# mainboard.net
KiCad netlist of a schematic drawn in EAGLE
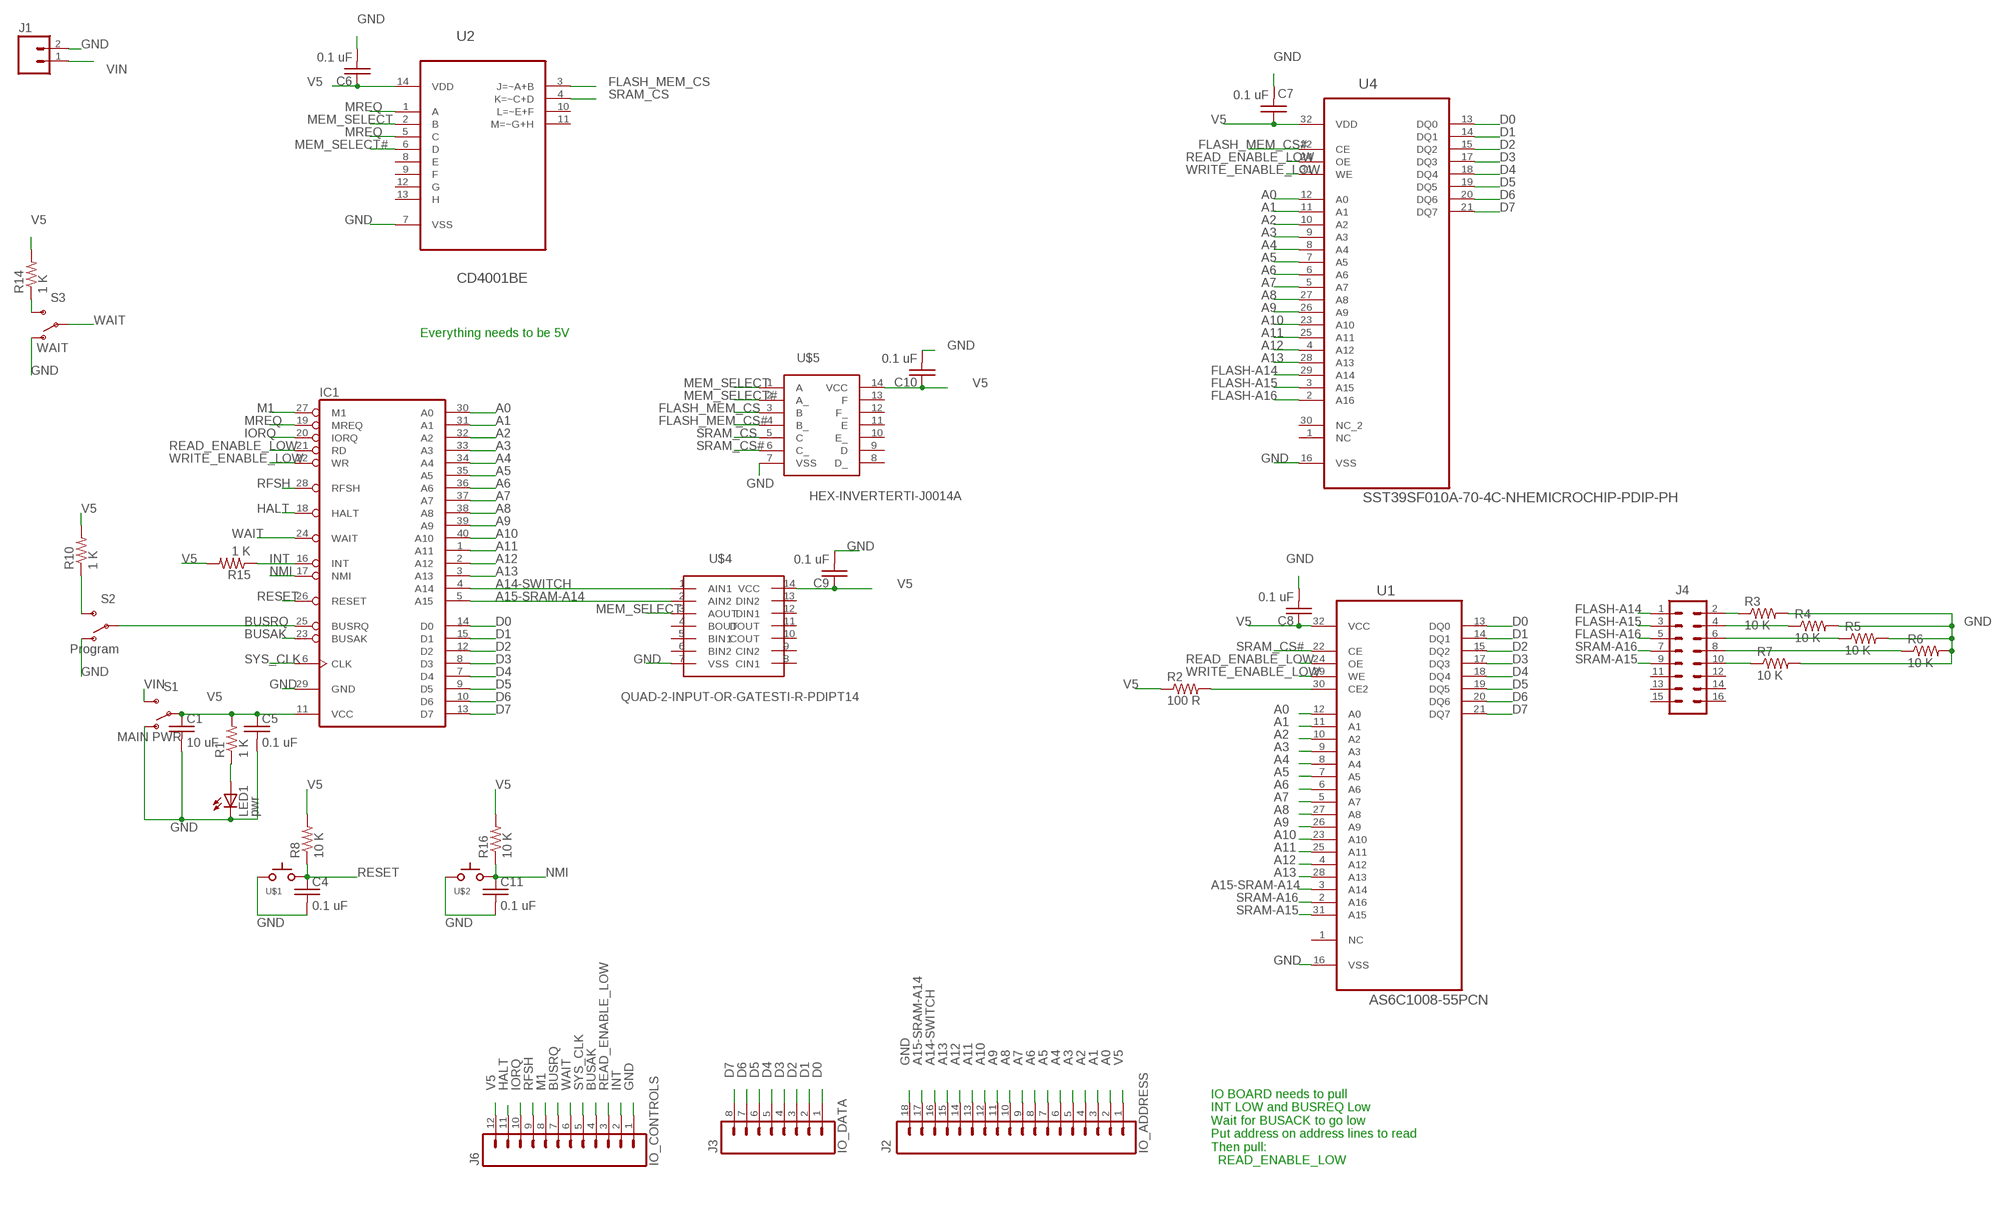
[diagram p0: schematic, sheet 1]
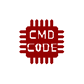
[diagram p1: schematic, sheet 2]

(export (version "E")
  (design (tool "Eeschema 10.0.6"))
  (components
    (comp (ref "C1")
      (value "10 uF")
      (footprint "eagle-import:C0805K")
      (libsource (lib "eagle-import") (part "C-USC0805K"))
    )
    (comp (ref "C4")
      (value "0.1 uF")
      (footprint "eagle-import:C0805K")
      (libsource (lib "eagle-import") (part "C-USC0805K"))
    )
    (comp (ref "C5")
      (value "0.1 uF")
      (footprint "eagle-import:C0805K")
      (libsource (lib "eagle-import") (part "C-USC0805K"))
    )
    (comp (ref "C6")
      (value "0.1 uF")
      (footprint "eagle-import:C0805K")
      (libsource (lib "eagle-import") (part "C-USC0805K"))
    )
    (comp (ref "C7")
      (value "0.1 uF")
      (footprint "eagle-import:C0805K")
      (libsource (lib "eagle-import") (part "C-USC0805K"))
    )
    (comp (ref "C8")
      (value "0.1 uF")
      (footprint "eagle-import:C0805K")
      (libsource (lib "eagle-import") (part "C-USC0805K"))
    )
    (comp (ref "C9")
      (value "0.1 uF")
      (footprint "eagle-import:C0805K")
      (libsource (lib "eagle-import") (part "C-USC0805K"))
    )
    (comp (ref "C10")
      (value "0.1 uF")
      (footprint "eagle-import:C0805K")
      (libsource (lib "eagle-import") (part "C-USC0805K"))
    )
    (comp (ref "C11")
      (value "0.1 uF")
      (footprint "eagle-import:C0805K")
      (libsource (lib "eagle-import") (part "C-USC0805K"))
    )
    (comp (ref "IC1")
      (value "Z80CPU")
      (footprint "eagle-import:DIL40")
      (libsource (lib "eagle-import") (part "Z80CPU"))
    )
    (comp (ref "J1")
      (value "M02PTH")
      (footprint "eagle-import:1X02")
      (libsource (lib "eagle-import") (part "M02PTH"))
    )
    (comp (ref "J2")
      (value "IO_ADDRESS")
      (footprint "eagle-import:1X18")
      (libsource (lib "eagle-import") (part "M18_"))
    )
    (comp (ref "J3")
      (value "IO_DATA")
      (footprint "eagle-import:1X08_LOCK_LONGPADS")
      (libsource (lib "eagle-import") (part "M08LOCK_LONGPADS"))
    )
    (comp (ref "J4")
      (value "M08X2")
      (footprint "eagle-import:2X8")
      (libsource (lib "eagle-import") (part "M08X2"))
    )
    (comp (ref "J6")
      (value "IO_CONTROLS")
      (footprint "eagle-import:1X12_LONGPADS")
      (libsource (lib "eagle-import") (part "M12LONGPADS"))
    )
    (comp (ref "LED1")
      (value "pwr")
      (footprint "eagle-import:LED-1206")
      (libsource (lib "eagle-import") (part "LED1206"))
    )
    (comp (ref "R1")
      (value "1 K")
      (footprint "eagle-import:0805")
      (libsource (lib "eagle-import") (part "RESISTOR0805-RES"))
    )
    (comp (ref "R2")
      (value "100 R")
      (footprint "eagle-import:0805")
      (libsource (lib "eagle-import") (part "RESISTOR0805-RES"))
    )
    (comp (ref "R3")
      (value "10 K")
      (footprint "eagle-import:0805")
      (libsource (lib "eagle-import") (part "RESISTOR0805-RES"))
    )
    (comp (ref "R4")
      (value "10 K")
      (footprint "eagle-import:0805")
      (libsource (lib "eagle-import") (part "RESISTOR0805-RES"))
    )
    (comp (ref "R5")
      (value "10 K")
      (footprint "eagle-import:0805")
      (libsource (lib "eagle-import") (part "RESISTOR0805-RES"))
    )
    (comp (ref "R6")
      (value "10 K")
      (footprint "eagle-import:0805")
      (libsource (lib "eagle-import") (part "RESISTOR0805-RES"))
    )
    (comp (ref "R7")
      (value "10 K")
      (footprint "eagle-import:0805")
      (libsource (lib "eagle-import") (part "RESISTOR0805-RES"))
    )
    (comp (ref "R8")
      (value "10 K")
      (footprint "eagle-import:0805")
      (libsource (lib "eagle-import") (part "RESISTOR0805-RES"))
    )
    (comp (ref "R10")
      (value "1 K")
      (footprint "eagle-import:0805")
      (libsource (lib "eagle-import") (part "RESISTOR0805-RES"))
    )
    (comp (ref "R14")
      (value "1 K")
      (footprint "eagle-import:0805")
      (libsource (lib "eagle-import") (part "RESISTOR0805-RES"))
    )
    (comp (ref "R15")
      (value "1 K")
      (footprint "eagle-import:0805")
      (libsource (lib "eagle-import") (part "RESISTOR0805-RES"))
    )
    (comp (ref "R16")
      (value "10 K")
      (footprint "eagle-import:0805")
      (libsource (lib "eagle-import") (part "RESISTOR0805-RES"))
    )
    (comp (ref "S1")
      (value "MAIN PWR")
      (footprint "eagle-import:SWITCH-SPDT_KIT")
      (libsource (lib "eagle-import") (part "SWITCH-SPSTKIT"))
    )
    (comp (ref "S2")
      (value "Program")
      (footprint "eagle-import:SWITCH-SPDT_KIT")
      (libsource (lib "eagle-import") (part "SWITCH-SPSTKIT"))
    )
    (comp (ref "S3")
      (value "WAIT")
      (footprint "eagle-import:SWITCH-SPDT_KIT")
      (libsource (lib "eagle-import") (part "SWITCH-SPSTKIT"))
    )
    (comp (ref "U$1")
      (value "SWITCH_TACTILETACTILE-2PIN-NARROW")
      (footprint "eagle-import:TACTILE-2PIN-NARROW")
      (libsource (lib "eagle-import") (part "SWITCH_TACTILETACTILE-2PIN-NARROW"))
    )
    (comp (ref "U$2")
      (value "SWITCH_TACTILETACTILE-2PIN-NARROW")
      (footprint "eagle-import:TACTILE-2PIN-NARROW")
      (libsource (lib "eagle-import") (part "SWITCH_TACTILETACTILE-2PIN-NARROW"))
    )
    (comp (ref "U$4")
      (value "QUAD-2-INPUT-OR-GATESTI-R-PDIPT14")
      (footprint "eagle-import:DIP762W36P254L1981H508Q14B")
      (libsource (lib "eagle-import") (part "QUAD-2-INPUT-OR-GATESTI-R-PDIPT14"))
    )
    (comp (ref "U$5")
      (value "HEX-INVERTERTI-J0014A")
      (footprint "eagle-import:DIP797W66P254L1954H508Q14B")
      (libsource (lib "eagle-import") (part "HEX-INVERTERTI-J0014A"))
    )
    (comp (ref "U1")
      (value "AS6C1008-55PCN")
      (footprint "eagle-import:DIP254P1524X393-32")
      (fields (field (name "MF") "Alliance Memory,"))
      (libsource (lib "eagle-import") (part "AS6C1008-55PCN"))
    )
    (comp (ref "U2")
      (value "CD4001BE")
      (footprint "eagle-import:DIP254P762X508-14")
      (fields (field (name "MF") "Texas Instruments"))
      (libsource (lib "eagle-import") (part "CD4001BE"))
    )
    (comp (ref "U4")
      (value "SST39SF010A-70-4C-NHEMICROCHIP-PDIP-PH")
      (footprint "eagle-import:DIP1574W53P254L4191H508Q32B")
      (fields (field (name "MP") "SST39SF010A-70-4C-NHE"))
      (libsource (lib "eagle-import") (part "SST39SF010A-70-4C-NHEMICROCHIP-PDIP-PH"))
    )
    (comp (ref "U$3")
      (value "CMD_C0DE_LOGOCMD_CODE_LOGO_SILK")
      (footprint "eagle-import:CMD_C0DE_LOGO_SILK")
      (libsource (lib "eagle-import") (part "CMD_C0DE_LOGOCMD_CODE_LOGO_SILK"))
    )
  )
  (nets
    (net (code "1") (name "A0") (class "Default")
      (node (ref "IC1") (pin "30") (pinfunction "A0_30") (pintype "output"))
      (node (ref "J2") (pin "2") (pinfunction "2_2") (pintype "passive"))
      (node (ref "U1") (pin "12") (pinfunction "A0_12") (pintype "input"))
      (node (ref "U4") (pin "12") (pinfunction "A0_12") (pintype "input"))
    )
    (net (code "2") (name "A1") (class "Default")
      (node (ref "IC1") (pin "31") (pinfunction "A1_31") (pintype "output"))
      (node (ref "J2") (pin "3") (pinfunction "3_3") (pintype "passive"))
      (node (ref "U1") (pin "11") (pinfunction "A1_11") (pintype "input"))
      (node (ref "U4") (pin "11") (pinfunction "A1_11") (pintype "input"))
    )
    (net (code "3") (name "A2") (class "Default")
      (node (ref "IC1") (pin "32") (pinfunction "A2_32") (pintype "output"))
      (node (ref "J2") (pin "4") (pinfunction "4_4") (pintype "passive"))
      (node (ref "U1") (pin "10") (pinfunction "A2_10") (pintype "input"))
      (node (ref "U4") (pin "10") (pinfunction "A2_10") (pintype "input"))
    )
    (net (code "4") (name "A3") (class "Default")
      (node (ref "IC1") (pin "33") (pinfunction "A3_33") (pintype "output"))
      (node (ref "J2") (pin "5") (pinfunction "5_5") (pintype "passive"))
      (node (ref "U1") (pin "9") (pinfunction "A3_9") (pintype "input"))
      (node (ref "U4") (pin "9") (pinfunction "A3_9") (pintype "input"))
    )
    (net (code "5") (name "A4") (class "Default")
      (node (ref "IC1") (pin "34") (pinfunction "A4_34") (pintype "output"))
      (node (ref "J2") (pin "6") (pinfunction "6_6") (pintype "passive"))
      (node (ref "U1") (pin "8") (pinfunction "A4_8") (pintype "input"))
      (node (ref "U4") (pin "8") (pinfunction "A4_8") (pintype "input"))
    )
    (net (code "6") (name "A5") (class "Default")
      (node (ref "IC1") (pin "35") (pinfunction "A5_35") (pintype "output"))
      (node (ref "J2") (pin "7") (pinfunction "7_7") (pintype "passive"))
      (node (ref "U1") (pin "7") (pinfunction "A5_7") (pintype "input"))
      (node (ref "U4") (pin "7") (pinfunction "A5_7") (pintype "input"))
    )
    (net (code "7") (name "A6") (class "Default")
      (node (ref "IC1") (pin "36") (pinfunction "A6_36") (pintype "output"))
      (node (ref "J2") (pin "8") (pinfunction "8_8") (pintype "passive"))
      (node (ref "U1") (pin "6") (pinfunction "A6_6") (pintype "input"))
      (node (ref "U4") (pin "6") (pinfunction "A6_6") (pintype "input"))
    )
    (net (code "8") (name "A7") (class "Default")
      (node (ref "IC1") (pin "37") (pinfunction "A7_37") (pintype "output"))
      (node (ref "J2") (pin "9") (pinfunction "9_9") (pintype "passive"))
      (node (ref "U1") (pin "5") (pinfunction "A7_5") (pintype "input"))
      (node (ref "U4") (pin "5") (pinfunction "A7_5") (pintype "input"))
    )
    (net (code "9") (name "A8") (class "Default")
      (node (ref "IC1") (pin "38") (pinfunction "A8_38") (pintype "output"))
      (node (ref "J2") (pin "10") (pinfunction "10_10") (pintype "passive"))
      (node (ref "U1") (pin "27") (pinfunction "A8_27") (pintype "input"))
      (node (ref "U4") (pin "27") (pinfunction "A8_27") (pintype "input"))
    )
    (net (code "10") (name "A9") (class "Default")
      (node (ref "IC1") (pin "39") (pinfunction "A9_39") (pintype "output"))
      (node (ref "J2") (pin "11") (pinfunction "11_11") (pintype "passive"))
      (node (ref "U1") (pin "26") (pinfunction "A9_26") (pintype "input"))
      (node (ref "U4") (pin "26") (pinfunction "A9_26") (pintype "input"))
    )
    (net (code "11") (name "A10") (class "Default")
      (node (ref "IC1") (pin "40") (pinfunction "A10_40") (pintype "output"))
      (node (ref "J2") (pin "12") (pinfunction "12_12") (pintype "passive"))
      (node (ref "U1") (pin "23") (pinfunction "A10_23") (pintype "input"))
      (node (ref "U4") (pin "23") (pinfunction "A10_23") (pintype "input"))
    )
    (net (code "12") (name "A11") (class "Default")
      (node (ref "IC1") (pin "1") (pinfunction "A11_1") (pintype "output"))
      (node (ref "J2") (pin "13") (pinfunction "13_13") (pintype "passive"))
      (node (ref "U1") (pin "25") (pinfunction "A11_25") (pintype "input"))
      (node (ref "U4") (pin "25") (pinfunction "A11_25") (pintype "input"))
    )
    (net (code "13") (name "A12") (class "Default")
      (node (ref "IC1") (pin "2") (pinfunction "A12_2") (pintype "output"))
      (node (ref "J2") (pin "14") (pinfunction "14_14") (pintype "passive"))
      (node (ref "U1") (pin "4") (pinfunction "A12_4") (pintype "input"))
      (node (ref "U4") (pin "4") (pinfunction "A12_4") (pintype "input"))
    )
    (net (code "14") (name "A13") (class "Default")
      (node (ref "IC1") (pin "3") (pinfunction "A13_3") (pintype "output"))
      (node (ref "J2") (pin "15") (pinfunction "15_15") (pintype "passive"))
      (node (ref "U1") (pin "28") (pinfunction "A13_28") (pintype "input"))
      (node (ref "U4") (pin "28") (pinfunction "A13_28") (pintype "input"))
    )
    (net (code "15") (name "A14-SWITCH") (class "Default")
      (node (ref "IC1") (pin "4") (pinfunction "A14_4") (pintype "output"))
      (node (ref "J2") (pin "16") (pinfunction "16_16") (pintype "passive"))
      (node (ref "U$4") (pin "1") (pinfunction "AIN1_1") (pintype "input"))
    )
    (net (code "16") (name "A15-SRAM-A14") (class "Default")
      (node (ref "IC1") (pin "5") (pinfunction "A15_5") (pintype "output"))
      (node (ref "J2") (pin "17") (pinfunction "17_17") (pintype "passive"))
      (node (ref "U$4") (pin "2") (pinfunction "AIN2_2") (pintype "input"))
      (node (ref "U1") (pin "3") (pinfunction "A14_3") (pintype "input"))
    )
    (net (code "17") (name "BUSAK") (class "Default")
      (node (ref "IC1") (pin "23") (pinfunction "BUSAK_23") (pintype "output"))
      (node (ref "J6") (pin "4") (pinfunction "4_4") (pintype "passive"))
    )
    (net (code "18") (name "BUSRQ") (class "Default")
      (node (ref "IC1") (pin "25") (pinfunction "BUSRQ_25") (pintype "input"))
      (node (ref "J6") (pin "7") (pinfunction "7_7") (pintype "passive"))
      (node (ref "S2") (pin "2") (pinfunction "P_2") (pintype "passive"))
    )
    (net (code "19") (name "D0") (class "Default")
      (node (ref "IC1") (pin "14") (pinfunction "D0_14") (pintype "bidirectional"))
      (node (ref "J3") (pin "1") (pinfunction "1_1") (pintype "passive"))
      (node (ref "U1") (pin "13") (pinfunction "DQ0_13") (pintype "bidirectional"))
      (node (ref "U4") (pin "13") (pinfunction "DQ0_13") (pintype "output"))
    )
    (net (code "20") (name "D1") (class "Default")
      (node (ref "IC1") (pin "15") (pinfunction "D1_15") (pintype "bidirectional"))
      (node (ref "J3") (pin "2") (pinfunction "2_2") (pintype "passive"))
      (node (ref "U1") (pin "14") (pinfunction "DQ1_14") (pintype "bidirectional"))
      (node (ref "U4") (pin "14") (pinfunction "DQ1_14") (pintype "output"))
    )
    (net (code "21") (name "D2") (class "Default")
      (node (ref "IC1") (pin "12") (pinfunction "D2_12") (pintype "bidirectional"))
      (node (ref "J3") (pin "3") (pinfunction "3_3") (pintype "passive"))
      (node (ref "U1") (pin "15") (pinfunction "DQ2_15") (pintype "bidirectional"))
      (node (ref "U4") (pin "15") (pinfunction "DQ2_15") (pintype "output"))
    )
    (net (code "22") (name "D3") (class "Default")
      (node (ref "IC1") (pin "8") (pinfunction "D3_8") (pintype "bidirectional"))
      (node (ref "J3") (pin "4") (pinfunction "4_4") (pintype "passive"))
      (node (ref "U1") (pin "17") (pinfunction "DQ3_17") (pintype "bidirectional"))
      (node (ref "U4") (pin "17") (pinfunction "DQ3_17") (pintype "output"))
    )
    (net (code "23") (name "D4") (class "Default")
      (node (ref "IC1") (pin "7") (pinfunction "D4_7") (pintype "bidirectional"))
      (node (ref "J3") (pin "5") (pinfunction "5_5") (pintype "passive"))
      (node (ref "U1") (pin "18") (pinfunction "DQ4_18") (pintype "bidirectional"))
      (node (ref "U4") (pin "18") (pinfunction "DQ4_18") (pintype "output"))
    )
    (net (code "24") (name "D5") (class "Default")
      (node (ref "IC1") (pin "9") (pinfunction "D5_9") (pintype "bidirectional"))
      (node (ref "J3") (pin "6") (pinfunction "6_6") (pintype "passive"))
      (node (ref "U1") (pin "19") (pinfunction "DQ5_19") (pintype "bidirectional"))
      (node (ref "U4") (pin "19") (pinfunction "DQ5_19") (pintype "output"))
    )
    (net (code "25") (name "D6") (class "Default")
      (node (ref "IC1") (pin "10") (pinfunction "D6_10") (pintype "bidirectional"))
      (node (ref "J3") (pin "7") (pinfunction "7_7") (pintype "passive"))
      (node (ref "U1") (pin "20") (pinfunction "DQ6_20") (pintype "bidirectional"))
      (node (ref "U4") (pin "20") (pinfunction "DQ6_20") (pintype "output"))
    )
    (net (code "26") (name "D7") (class "Default")
      (node (ref "IC1") (pin "13") (pinfunction "D7_13") (pintype "bidirectional"))
      (node (ref "J3") (pin "8") (pinfunction "8_8") (pintype "passive"))
      (node (ref "U1") (pin "21") (pinfunction "DQ7_21") (pintype "bidirectional"))
      (node (ref "U4") (pin "21") (pinfunction "DQ7_21") (pintype "output"))
    )
    (net (code "27") (name "FLASH-A14") (class "Default")
      (node (ref "J4") (pin "1") (pinfunction "1_1") (pintype "passive"))
      (node (ref "U4") (pin "29") (pinfunction "A14_29") (pintype "input"))
    )
    (net (code "28") (name "FLASH-A15") (class "Default")
      (node (ref "J4") (pin "3") (pinfunction "3_3") (pintype "passive"))
      (node (ref "U4") (pin "3") (pinfunction "A15_3") (pintype "input"))
    )
    (net (code "29") (name "FLASH-A16") (class "Default")
      (node (ref "J4") (pin "5") (pinfunction "5_5") (pintype "passive"))
      (node (ref "U4") (pin "2") (pinfunction "A16_2") (pintype "input"))
    )
    (net (code "30") (name "FLASH_MEM_CS") (class "Default")
      (node (ref "U$5") (pin "3") (pinfunction "B_3") (pintype "input"))
      (node (ref "U2") (pin "3") (pinfunction "J=~{A+B}_3") (pintype "output"))
    )
    (net (code "31") (name "FLASH_MEM_CS#") (class "Default")
      (node (ref "U$5") (pin "4") (pinfunction "B__4") (pintype "output"))
      (node (ref "U4") (pin "22") (pinfunction "CE_22") (pintype "input"))
    )
    (net (code "32") (name "GND") (class "Default")
      (node (ref "C1") (pin "2") (pinfunction "2_2") (pintype "passive"))
      (node (ref "C10") (pin "2") (pinfunction "2_2") (pintype "passive"))
      (node (ref "C11") (pin "2") (pinfunction "2_2") (pintype "passive"))
      (node (ref "C4") (pin "2") (pinfunction "2_2") (pintype "passive"))
      (node (ref "C5") (pin "2") (pinfunction "2_2") (pintype "passive"))
      (node (ref "C6") (pin "2") (pinfunction "2_2") (pintype "passive"))
      (node (ref "C7") (pin "2") (pinfunction "2_2") (pintype "passive"))
      (node (ref "C8") (pin "2") (pinfunction "2_2") (pintype "passive"))
      (node (ref "C9") (pin "2") (pinfunction "2_2") (pintype "passive"))
      (node (ref "IC1") (pin "29") (pinfunction "GND_29") (pintype "power_in"))
      (node (ref "J1") (pin "2") (pinfunction "2_2") (pintype "passive"))
      (node (ref "J2") (pin "18") (pinfunction "18_18") (pintype "passive"))
      (node (ref "J6") (pin "1") (pinfunction "1_1") (pintype "passive"))
      (node (ref "LED1") (pin "C") (pinfunction "C_C") (pintype "output"))
      (node (ref "R3") (pin "2") (pinfunction "2_2") (pintype "passive"))
      (node (ref "R4") (pin "2") (pinfunction "2_2") (pintype "passive"))
      (node (ref "R5") (pin "2") (pinfunction "2_2") (pintype "passive"))
      (node (ref "R6") (pin "2") (pinfunction "2_2") (pintype "passive"))
      (node (ref "R7") (pin "2") (pinfunction "2_2") (pintype "passive"))
      (node (ref "S1") (pin "1") (pinfunction "O_1") (pintype "passive"))
      (node (ref "S2") (pin "1") (pinfunction "O_1") (pintype "passive"))
      (node (ref "S3") (pin "1") (pinfunction "O_1") (pintype "passive"))
      (node (ref "U$1") (pin "P$2") (pinfunction "C_P$2") (pintype "passive"))
      (node (ref "U$2") (pin "P$2") (pinfunction "C_P$2") (pintype "passive"))
      (node (ref "U$4") (pin "7") (pinfunction "VSS_7") (pintype "power_in"))
      (node (ref "U$5") (pin "7") (pinfunction "VSS_7") (pintype "power_in"))
      (node (ref "U1") (pin "16") (pinfunction "VSS_16") (pintype "bidirectional"))
      (node (ref "U2") (pin "7") (pinfunction "VSS_7") (pintype "power_in"))
      (node (ref "U4") (pin "16") (pinfunction "VSS_16") (pintype "passive"))
    )
    (net (code "33") (name "HALT") (class "Default")
      (node (ref "IC1") (pin "18") (pinfunction "HALT_18") (pintype "output"))
      (node (ref "J6") (pin "11") (pinfunction "11_11") (pintype "passive"))
    )
    (net (code "34") (name "INT") (class "Default")
      (node (ref "IC1") (pin "16") (pinfunction "INT_16") (pintype "input"))
      (node (ref "J6") (pin "2") (pinfunction "2_2") (pintype "passive"))
      (node (ref "R15") (pin "1") (pinfunction "1_1") (pintype "passive"))
    )
    (net (code "35") (name "IORQ") (class "Default")
      (node (ref "IC1") (pin "20") (pinfunction "IORQ_20") (pintype "output"))
      (node (ref "J6") (pin "10") (pinfunction "10_10") (pintype "passive"))
    )
    (net (code "36") (name "M1") (class "Default")
      (node (ref "IC1") (pin "27") (pinfunction "M1_27") (pintype "output"))
      (node (ref "J6") (pin "8") (pinfunction "8_8") (pintype "passive"))
    )
    (net (code "37") (name "MEM_SELECT") (class "Default")
      (node (ref "U$4") (pin "3") (pinfunction "AOUT_3") (pintype "output"))
      (node (ref "U$5") (pin "1") (pinfunction "A_1") (pintype "input"))
      (node (ref "U2") (pin "2") (pinfunction "B_2") (pintype "input"))
    )
    (net (code "38") (name "MEM_SELECT#") (class "Default")
      (node (ref "U$5") (pin "2") (pinfunction "A__2") (pintype "output"))
      (node (ref "U2") (pin "6") (pinfunction "D_6") (pintype "input"))
    )
    (net (code "39") (name "MREQ") (class "Default")
      (node (ref "IC1") (pin "19") (pinfunction "MREQ_19") (pintype "output"))
      (node (ref "U2") (pin "1") (pinfunction "A_1") (pintype "input"))
      (node (ref "U2") (pin "5") (pinfunction "C_5") (pintype "input"))
    )
    (net (code "40") (name "NMI") (class "Default")
      (node (ref "C11") (pin "1") (pinfunction "1_1") (pintype "passive"))
      (node (ref "IC1") (pin "17") (pinfunction "NMI_17") (pintype "input"))
      (node (ref "R16") (pin "1") (pinfunction "1_1") (pintype "passive"))
      (node (ref "U$2") (pin "P$1") (pinfunction "A_P$1") (pintype "passive"))
    )
    (net (code "41") (name "Net-(J4-Pad2)") (class "Default")
      (node (ref "J4") (pin "2") (pinfunction "2_2") (pintype "passive"))
      (node (ref "R3") (pin "1") (pinfunction "1_1") (pintype "passive"))
    )
    (net (code "42") (name "Net-(J4-Pad4)") (class "Default")
      (node (ref "J4") (pin "4") (pinfunction "4_4") (pintype "passive"))
      (node (ref "R4") (pin "1") (pinfunction "1_1") (pintype "passive"))
    )
    (net (code "43") (name "Net-(J4-Pad6)") (class "Default")
      (node (ref "J4") (pin "6") (pinfunction "6_6") (pintype "passive"))
      (node (ref "R5") (pin "1") (pinfunction "1_1") (pintype "passive"))
    )
    (net (code "44") (name "Net-(J4-Pad8)") (class "Default")
      (node (ref "J4") (pin "8") (pinfunction "8_8") (pintype "passive"))
      (node (ref "R6") (pin "1") (pinfunction "1_1") (pintype "passive"))
    )
    (net (code "45") (name "Net-(J4-Pad10)") (class "Default")
      (node (ref "J4") (pin "10") (pinfunction "10_10") (pintype "passive"))
      (node (ref "R7") (pin "1") (pinfunction "1_1") (pintype "passive"))
    )
    (net (code "46") (name "Net-(LED1-PadA)") (class "Default")
      (node (ref "LED1") (pin "A") (pinfunction "A_A") (pintype "input"))
      (node (ref "R1") (pin "1") (pinfunction "1_1") (pintype "passive"))
    )
    (net (code "47") (name "Net-(S2-S)") (class "Default")
      (node (ref "R10") (pin "1") (pinfunction "1_1") (pintype "passive"))
      (node (ref "S2") (pin "3") (pinfunction "S_3") (pintype "passive"))
    )
    (net (code "48") (name "Net-(S3-S)") (class "Default")
      (node (ref "R14") (pin "1") (pinfunction "1_1") (pintype "passive"))
      (node (ref "S3") (pin "3") (pinfunction "S_3") (pintype "passive"))
    )
    (net (code "49") (name "Net-(U1-CE2)") (class "Default")
      (node (ref "R2") (pin "2") (pinfunction "2_2") (pintype "passive"))
      (node (ref "U1") (pin "30") (pinfunction "CE2_30") (pintype "input"))
    )
    (net (code "50") (name "READ_ENABLE_LOW") (class "Default")
      (node (ref "IC1") (pin "21") (pinfunction "RD_21") (pintype "output"))
      (node (ref "J6") (pin "3") (pinfunction "3_3") (pintype "passive"))
      (node (ref "U1") (pin "24") (pinfunction "OE_24") (pintype "input"))
      (node (ref "U4") (pin "24") (pinfunction "OE_24") (pintype "input"))
    )
    (net (code "51") (name "RESET") (class "Default")
      (node (ref "C4") (pin "1") (pinfunction "1_1") (pintype "passive"))
      (node (ref "IC1") (pin "26") (pinfunction "RESET_26") (pintype "input"))
      (node (ref "R8") (pin "1") (pinfunction "1_1") (pintype "passive"))
      (node (ref "U$1") (pin "P$1") (pinfunction "A_P$1") (pintype "passive"))
    )
    (net (code "52") (name "RFSH") (class "Default")
      (node (ref "IC1") (pin "28") (pinfunction "RFSH_28") (pintype "output"))
      (node (ref "J6") (pin "9") (pinfunction "9_9") (pintype "passive"))
    )
    (net (code "53") (name "SRAM-A15") (class "Default")
      (node (ref "J4") (pin "9") (pinfunction "9_9") (pintype "passive"))
      (node (ref "U1") (pin "31") (pinfunction "A15_31") (pintype "input"))
    )
    (net (code "54") (name "SRAM-A16") (class "Default")
      (node (ref "J4") (pin "7") (pinfunction "7_7") (pintype "passive"))
      (node (ref "U1") (pin "2") (pinfunction "A16_2") (pintype "input"))
    )
    (net (code "55") (name "SRAM_CS") (class "Default")
      (node (ref "U$5") (pin "5") (pinfunction "C_5") (pintype "input"))
      (node (ref "U2") (pin "4") (pinfunction "K=~{C+D}_4") (pintype "output"))
    )
    (net (code "56") (name "SRAM_CS#") (class "Default")
      (node (ref "U$5") (pin "6") (pinfunction "C__6") (pintype "output"))
      (node (ref "U1") (pin "22") (pinfunction "CE_22") (pintype "input"))
    )
    (net (code "57") (name "SYS_CLK") (class "Default")
      (node (ref "IC1") (pin "6") (pinfunction "CLK_6") (pintype "input"))
      (node (ref "J6") (pin "5") (pinfunction "5_5") (pintype "passive"))
    )
    (net (code "58") (name "V5") (class "Default")
      (node (ref "C1") (pin "1") (pinfunction "1_1") (pintype "passive"))
      (node (ref "C10") (pin "1") (pinfunction "1_1") (pintype "passive"))
      (node (ref "C5") (pin "1") (pinfunction "1_1") (pintype "passive"))
      (node (ref "C6") (pin "1") (pinfunction "1_1") (pintype "passive"))
      (node (ref "C7") (pin "1") (pinfunction "1_1") (pintype "passive"))
      (node (ref "C8") (pin "1") (pinfunction "1_1") (pintype "passive"))
      (node (ref "C9") (pin "1") (pinfunction "1_1") (pintype "passive"))
      (node (ref "IC1") (pin "11") (pinfunction "VCC_11") (pintype "power_in"))
      (node (ref "J2") (pin "1") (pinfunction "1_1") (pintype "passive"))
      (node (ref "J6") (pin "12") (pinfunction "12_12") (pintype "passive"))
      (node (ref "R1") (pin "2") (pinfunction "2_2") (pintype "passive"))
      (node (ref "R10") (pin "2") (pinfunction "2_2") (pintype "passive"))
      (node (ref "R14") (pin "2") (pinfunction "2_2") (pintype "passive"))
      (node (ref "R15") (pin "2") (pinfunction "2_2") (pintype "passive"))
      (node (ref "R16") (pin "2") (pinfunction "2_2") (pintype "passive"))
      (node (ref "R2") (pin "1") (pinfunction "1_1") (pintype "passive"))
      (node (ref "R8") (pin "2") (pinfunction "2_2") (pintype "passive"))
      (node (ref "S1") (pin "2") (pinfunction "P_2") (pintype "passive"))
      (node (ref "U$4") (pin "14") (pinfunction "VCC_14") (pintype "bidirectional"))
      (node (ref "U$5") (pin "14") (pinfunction "VCC_14") (pintype "power_in"))
      (node (ref "U1") (pin "32") (pinfunction "VCC_32") (pintype "power_in"))
      (node (ref "U2") (pin "14") (pinfunction "VDD_14") (pintype "power_in"))
      (node (ref "U4") (pin "32") (pinfunction "VDD_32") (pintype "power_in"))
    )
    (net (code "59") (name "VIN") (class "Default")
      (node (ref "J1") (pin "1") (pinfunction "1_1") (pintype "passive"))
      (node (ref "S1") (pin "3") (pinfunction "S_3") (pintype "passive"))
    )
    (net (code "60") (name "WAIT") (class "Default")
      (node (ref "IC1") (pin "24") (pinfunction "WAIT_24") (pintype "input"))
      (node (ref "J6") (pin "6") (pinfunction "6_6") (pintype "passive"))
      (node (ref "S3") (pin "2") (pinfunction "P_2") (pintype "passive"))
    )
    (net (code "61") (name "WRITE_ENABLE_LOW") (class "Default")
      (node (ref "IC1") (pin "22") (pinfunction "WR_22") (pintype "output"))
      (node (ref "U1") (pin "29") (pinfunction "WE_29") (pintype "input"))
      (node (ref "U4") (pin "31") (pinfunction "WE_31") (pintype "input"))
    )
    (net (code "62") (name "unconnected-(J4-Pad11)") (class "Default")
      (node (ref "J4") (pin "11") (pinfunction "11_11") (pintype "passive"))
    )
    (net (code "63") (name "unconnected-(J4-Pad12)") (class "Default")
      (node (ref "J4") (pin "12") (pinfunction "12_12") (pintype "passive"))
    )
    (net (code "64") (name "unconnected-(J4-Pad13)") (class "Default")
      (node (ref "J4") (pin "13") (pinfunction "13_13") (pintype "passive"))
    )
    (net (code "65") (name "unconnected-(J4-Pad14)") (class "Default")
      (node (ref "J4") (pin "14") (pinfunction "14_14") (pintype "passive"))
    )
    (net (code "66") (name "unconnected-(J4-Pad15)") (class "Default")
      (node (ref "J4") (pin "15") (pinfunction "15_15") (pintype "passive"))
    )
    (net (code "67") (name "unconnected-(J4-Pad16)") (class "Default")
      (node (ref "J4") (pin "16") (pinfunction "16_16") (pintype "passive"))
    )
    (net (code "68") (name "unconnected-(U$4-BIN1-Pad5)") (class "Default")
      (node (ref "U$4") (pin "5") (pinfunction "BIN1_5") (pintype "input"))
    )
    (net (code "69") (name "unconnected-(U$4-BIN2-Pad6)") (class "Default")
      (node (ref "U$4") (pin "6") (pinfunction "BIN2_6") (pintype "input"))
    )
    (net (code "70") (name "unconnected-(U$4-BOUT-Pad4)") (class "Default")
      (node (ref "U$4") (pin "4") (pinfunction "BOUT_4") (pintype "output"))
    )
    (net (code "71") (name "unconnected-(U$4-CIN1-Pad8)") (class "Default")
      (node (ref "U$4") (pin "8") (pinfunction "CIN1_8") (pintype "input"))
    )
    (net (code "72") (name "unconnected-(U$4-CIN2-Pad9)") (class "Default")
      (node (ref "U$4") (pin "9") (pinfunction "CIN2_9") (pintype "input"))
    )
    (net (code "73") (name "unconnected-(U$4-COUT-Pad10)") (class "Default")
      (node (ref "U$4") (pin "10") (pinfunction "COUT_10") (pintype "output"))
    )
    (net (code "74") (name "unconnected-(U$4-DIN1-Pad12)") (class "Default")
      (node (ref "U$4") (pin "12") (pinfunction "DIN1_12") (pintype "input"))
    )
    (net (code "75") (name "unconnected-(U$4-DIN2-Pad13)") (class "Default")
      (node (ref "U$4") (pin "13") (pinfunction "DIN2_13") (pintype "input"))
    )
    (net (code "76") (name "unconnected-(U$4-DOUT-Pad11)") (class "Default")
      (node (ref "U$4") (pin "11") (pinfunction "DOUT_11") (pintype "output"))
    )
    (net (code "77") (name "unconnected-(U$5-D-Pad9)") (class "Default")
      (node (ref "U$5") (pin "9") (pinfunction "D_9") (pintype "input"))
    )
    (net (code "78") (name "unconnected-(U$5-D_-Pad8)") (class "Default")
      (node (ref "U$5") (pin "8") (pinfunction "D__8") (pintype "output"))
    )
    (net (code "79") (name "unconnected-(U$5-E-Pad11)") (class "Default")
      (node (ref "U$5") (pin "11") (pinfunction "E_11") (pintype "input"))
    )
    (net (code "80") (name "unconnected-(U$5-E_-Pad10)") (class "Default")
      (node (ref "U$5") (pin "10") (pinfunction "E__10") (pintype "output"))
    )
    (net (code "81") (name "unconnected-(U$5-F-Pad13)") (class "Default")
      (node (ref "U$5") (pin "13") (pinfunction "F_13") (pintype "input"))
    )
    (net (code "82") (name "unconnected-(U$5-F_-Pad12)") (class "Default")
      (node (ref "U$5") (pin "12") (pinfunction "F__12") (pintype "output"))
    )
    (net (code "83") (name "unconnected-(U1-NC-Pad1)") (class "Default")
      (node (ref "U1") (pin "1") (pinfunction "NC_1") (pintype "no_connect"))
    )
    (net (code "84") (name "unconnected-(U2-E-Pad8)") (class "Default")
      (node (ref "U2") (pin "8") (pinfunction "E_8") (pintype "input"))
    )
    (net (code "85") (name "unconnected-(U2-F-Pad9)") (class "Default")
      (node (ref "U2") (pin "9") (pinfunction "F_9") (pintype "input"))
    )
    (net (code "86") (name "unconnected-(U2-G-Pad12)") (class "Default")
      (node (ref "U2") (pin "12") (pinfunction "G_12") (pintype "input"))
    )
    (net (code "87") (name "unconnected-(U2-H-Pad13)") (class "Default")
      (node (ref "U2") (pin "13") (pinfunction "H_13") (pintype "input"))
    )
    (net (code "88") (name "unconnected-(U2-L=~{E+F}-Pad10)") (class "Default")
      (node (ref "U2") (pin "10") (pinfunction "L=~{E+F}_10") (pintype "output"))
    )
    (net (code "89") (name "unconnected-(U2-M=~{G+H}-Pad11)") (class "Default")
      (node (ref "U2") (pin "11") (pinfunction "M=~{G+H}_11") (pintype "output"))
    )
    (net (code "90") (name "unconnected-(U4-NC-Pad1)") (class "Default")
      (node (ref "U4") (pin "1") (pinfunction "NC_1") (pintype "no_connect"))
    )
    (net (code "91") (name "unconnected-(U4-NC_2-Pad30)") (class "Default")
      (node (ref "U4") (pin "30") (pinfunction "NC_2_30") (pintype "no_connect"))
    )
  )
)
